# ledshield.net
KiCad netlist of a schematic drawn in EAGLE
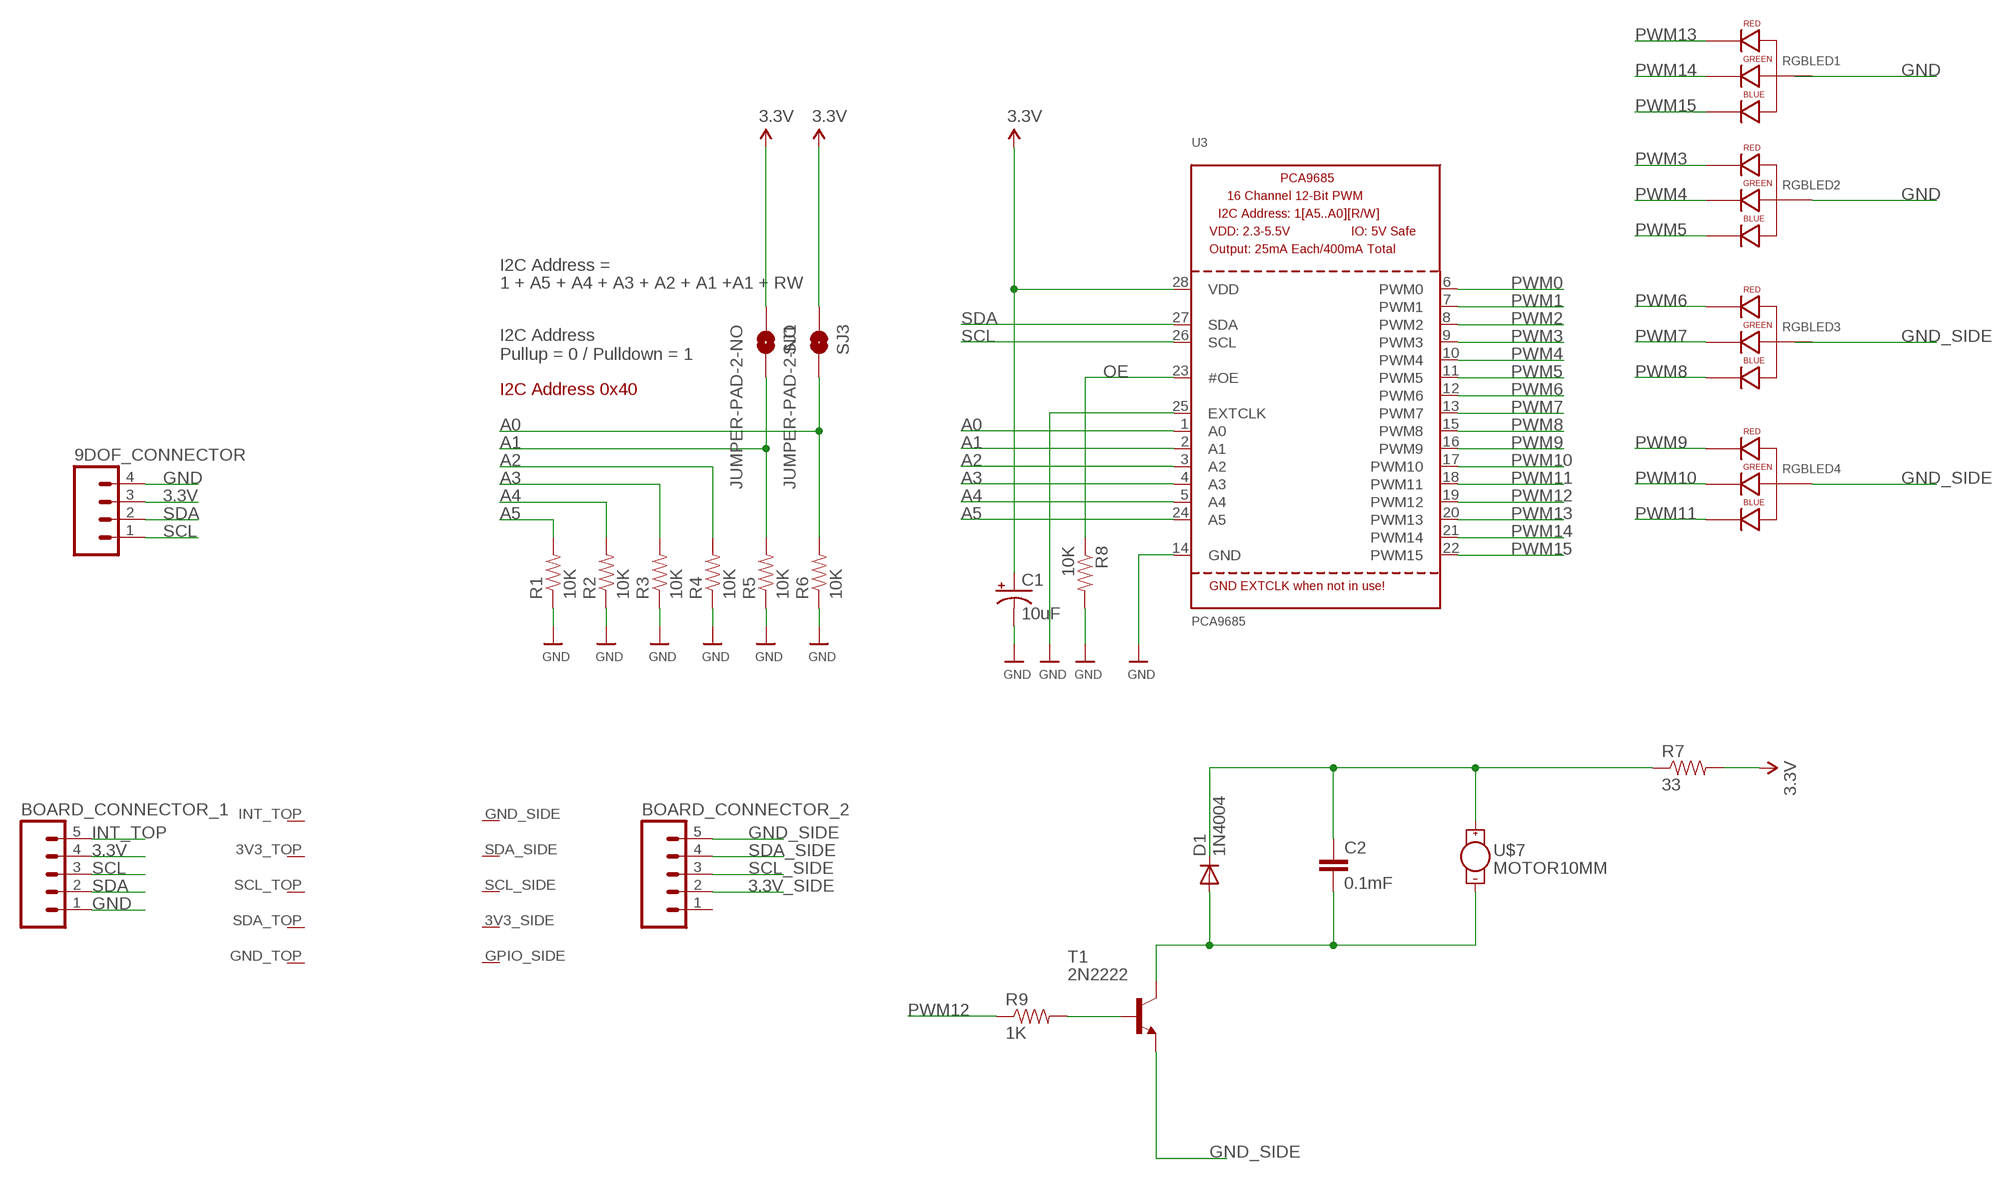
[diagram p0: schematic, sheet 1]

(export (version "E")
  (design (tool "Eeschema 10.0.6"))
  (components
    (comp (ref "9DOF_CONNECTOR")
      (value "M041.27MM")
      (footprint "eagle-import:1X04-1.27MM")
      (libsource (lib "eagle-import") (part "M041.27MM"))
    )
    (comp (ref "BOARD_CONNECTOR_1")
      (value "M051.27MM")
      (footprint "eagle-import:1X05-1.27MM")
      (libsource (lib "eagle-import") (part "M051.27MM"))
    )
    (comp (ref "BOARD_CONNECTOR_2")
      (value "M051.27MM")
      (footprint "eagle-import:1X05-1.27MM")
      (libsource (lib "eagle-import") (part "M051.27MM"))
    )
    (comp (ref "C1")
      (value "10uF")
      (footprint "eagle-import:EIA3216")
      (libsource (lib "eagle-import") (part "CAP_POL1206"))
    )
    (comp (ref "C2")
      (value "0.1mF")
      (footprint "eagle-import:1206")
      (libsource (lib "eagle-import") (part "CAP1206"))
    )
    (comp (ref "D1")
      (value "1N4004")
      (footprint "eagle-import:DO41-10")
      (libsource (lib "eagle-import") (part "1N4004"))
    )
    (comp (ref "R1")
      (value "10K")
      (footprint "eagle-import:1206")
      (libsource (lib "eagle-import") (part "RESISTOR1206"))
    )
    (comp (ref "R2")
      (value "10K")
      (footprint "eagle-import:1206")
      (libsource (lib "eagle-import") (part "RESISTOR1206"))
    )
    (comp (ref "R3")
      (value "10K")
      (footprint "eagle-import:1206")
      (libsource (lib "eagle-import") (part "RESISTOR1206"))
    )
    (comp (ref "R4")
      (value "10K")
      (footprint "eagle-import:1206")
      (libsource (lib "eagle-import") (part "RESISTOR1206"))
    )
    (comp (ref "R5")
      (value "10K")
      (footprint "eagle-import:1206")
      (libsource (lib "eagle-import") (part "RESISTOR1206"))
    )
    (comp (ref "R6")
      (value "10K")
      (footprint "eagle-import:1206")
      (libsource (lib "eagle-import") (part "RESISTOR1206"))
    )
    (comp (ref "R7")
      (value "33")
      (footprint "eagle-import:1206")
      (libsource (lib "eagle-import") (part "RESISTOR1206"))
    )
    (comp (ref "R8")
      (value "10K")
      (footprint "eagle-import:1206")
      (libsource (lib "eagle-import") (part "RESISTOR1206"))
    )
    (comp (ref "R9")
      (value "1K")
      (footprint "eagle-import:1206")
      (libsource (lib "eagle-import") (part "RESISTOR1206"))
    )
    (comp (ref "RGBLED1")
      (value "LED-RGB-CA-THRUCLEAR")
      (footprint "eagle-import:LED-RGB-THRU")
      (libsource (lib "eagle-import") (part "LED-RGB-CA-THRUCLEAR"))
    )
    (comp (ref "RGBLED2")
      (value "LED-RGB-CA-THRUCLEAR")
      (footprint "eagle-import:LED-RGB-THRU")
      (libsource (lib "eagle-import") (part "LED-RGB-CA-THRUCLEAR"))
    )
    (comp (ref "RGBLED3")
      (value "LED-RGB-CA-THRUCLEAR")
      (footprint "eagle-import:LED-RGB-THRU")
      (libsource (lib "eagle-import") (part "LED-RGB-CA-THRUCLEAR"))
    )
    (comp (ref "RGBLED4")
      (value "LED-RGB-CA-THRUCLEAR")
      (footprint "eagle-import:LED-RGB-THRU")
      (libsource (lib "eagle-import") (part "LED-RGB-CA-THRUCLEAR"))
    )
    (comp (ref "SJ1")
      (value "JUMPER-PAD-2-NO")
      (footprint "eagle-import:PAD-JUMPER-2-NO_NO_SILK")
      (libsource (lib "eagle-import") (part "JUMPER-PAD-2-NO"))
    )
    (comp (ref "SJ3")
      (value "JUMPER-PAD-2-NO")
      (footprint "eagle-import:PAD-JUMPER-2-NO_NO_SILK")
      (libsource (lib "eagle-import") (part "JUMPER-PAD-2-NO"))
    )
    (comp (ref "T1")
      (value "2N2222")
      (footprint "eagle-import:TO92-EBC-OVAL")
      (libsource (lib "eagle-import") (part "2N2222"))
    )
    (comp (ref "U$1")
      (value "IOT_MODULE_MAIN_V2_PTH")
      (footprint "eagle-import:IOT_MODULE_MAIN_V3_PTH")
      (libsource (lib "eagle-import") (part "IOT_MODULE_MAIN_V2_PTH"))
    )
    (comp (ref "U$7")
      (value "MOTOR10MM")
      (footprint "eagle-import:VIBE-MOTOR-10MM")
      (libsource (lib "eagle-import") (part "MOTOR10MM"))
    )
    (comp (ref "U3")
      (value "PCA9685")
      (footprint "eagle-import:TSSOP28")
      (libsource (lib "eagle-import") (part "PCA9685"))
    )
  )
  (nets
    (net (code "1") (name "/3.3V_SIDE") (class "Default")
      (node (ref "BOARD_CONNECTOR_2") (pin "2") (pinfunction "2_2") (pintype "passive"))
    )
    (net (code "2") (name "/A0") (class "Default")
      (node (ref "R6") (pin "2") (pinfunction "2_2") (pintype "passive"))
      (node (ref "SJ3") (pin "2") (pinfunction "2_2") (pintype "passive"))
      (node (ref "U3") (pin "1") (pinfunction "A0_1") (pintype "bidirectional"))
    )
    (net (code "3") (name "/A1") (class "Default")
      (node (ref "R5") (pin "2") (pinfunction "2_2") (pintype "passive"))
      (node (ref "SJ1") (pin "2") (pinfunction "2_2") (pintype "passive"))
      (node (ref "U3") (pin "2") (pinfunction "A1_2") (pintype "bidirectional"))
    )
    (net (code "4") (name "/A2") (class "Default")
      (node (ref "R4") (pin "2") (pinfunction "2_2") (pintype "passive"))
      (node (ref "U3") (pin "3") (pinfunction "A2_3") (pintype "bidirectional"))
    )
    (net (code "5") (name "/A3") (class "Default")
      (node (ref "R3") (pin "2") (pinfunction "2_2") (pintype "passive"))
      (node (ref "U3") (pin "4") (pinfunction "A3_4") (pintype "bidirectional"))
    )
    (net (code "6") (name "/A4") (class "Default")
      (node (ref "R2") (pin "2") (pinfunction "2_2") (pintype "passive"))
      (node (ref "U3") (pin "5") (pinfunction "A4_5") (pintype "bidirectional"))
    )
    (net (code "7") (name "/A5") (class "Default")
      (node (ref "R1") (pin "2") (pinfunction "2_2") (pintype "passive"))
      (node (ref "U3") (pin "24") (pinfunction "A5_24") (pintype "bidirectional"))
    )
    (net (code "8") (name "/GND_SIDE") (class "Default")
      (node (ref "BOARD_CONNECTOR_2") (pin "5") (pinfunction "5_5") (pintype "passive"))
      (node (ref "RGBLED4") (pin "2") (pinfunction "ANODE_2") (pintype "bidirectional"))
      (node (ref "T1") (pin "E") (pinfunction "E_E") (pintype "passive"))
    )
    (net (code "9") (name "/INT_TOP") (class "Default")
      (node (ref "BOARD_CONNECTOR_1") (pin "5") (pinfunction "5_5") (pintype "passive"))
    )
    (net (code "10") (name "/OE") (class "Default")
      (node (ref "R8") (pin "1") (pinfunction "1_1") (pintype "passive"))
      (node (ref "U3") (pin "23") (pinfunction "#OE_23") (pintype "input"))
    )
    (net (code "11") (name "/PWM0") (class "Default")
      (node (ref "U3") (pin "6") (pinfunction "PWM0_6") (pintype "output"))
    )
    (net (code "12") (name "/PWM1") (class "Default")
      (node (ref "U3") (pin "7") (pinfunction "PWM1_7") (pintype "output"))
    )
    (net (code "13") (name "/PWM2") (class "Default")
      (node (ref "U3") (pin "8") (pinfunction "PWM2_8") (pintype "output"))
    )
    (net (code "14") (name "/PWM3") (class "Default")
      (node (ref "RGBLED2") (pin "1") (pinfunction "RED_CATHODE_1") (pintype "bidirectional"))
      (node (ref "U3") (pin "9") (pinfunction "PWM3_9") (pintype "output"))
    )
    (net (code "15") (name "/PWM4") (class "Default")
      (node (ref "RGBLED2") (pin "3") (pinfunction "GREEN_CATHODE_3") (pintype "bidirectional"))
      (node (ref "U3") (pin "10") (pinfunction "PWM4_10") (pintype "output"))
    )
    (net (code "16") (name "/PWM5") (class "Default")
      (node (ref "RGBLED2") (pin "4") (pinfunction "BLUE_CATHODE_4") (pintype "bidirectional"))
      (node (ref "U3") (pin "11") (pinfunction "PWM5_11") (pintype "output"))
    )
    (net (code "17") (name "/PWM6") (class "Default")
      (node (ref "RGBLED3") (pin "1") (pinfunction "RED_CATHODE_1") (pintype "bidirectional"))
      (node (ref "U3") (pin "12") (pinfunction "PWM6_12") (pintype "output"))
    )
    (net (code "18") (name "/PWM7") (class "Default")
      (node (ref "RGBLED3") (pin "3") (pinfunction "GREEN_CATHODE_3") (pintype "bidirectional"))
      (node (ref "U3") (pin "13") (pinfunction "PWM7_13") (pintype "output"))
    )
    (net (code "19") (name "/PWM8") (class "Default")
      (node (ref "RGBLED3") (pin "4") (pinfunction "BLUE_CATHODE_4") (pintype "bidirectional"))
      (node (ref "U3") (pin "15") (pinfunction "PWM8_15") (pintype "output"))
    )
    (net (code "20") (name "/PWM9") (class "Default")
      (node (ref "RGBLED4") (pin "1") (pinfunction "RED_CATHODE_1") (pintype "bidirectional"))
      (node (ref "U3") (pin "16") (pinfunction "PWM9_16") (pintype "output"))
    )
    (net (code "21") (name "/PWM10") (class "Default")
      (node (ref "RGBLED4") (pin "3") (pinfunction "GREEN_CATHODE_3") (pintype "bidirectional"))
      (node (ref "U3") (pin "17") (pinfunction "PWM10_17") (pintype "output"))
    )
    (net (code "22") (name "/PWM11") (class "Default")
      (node (ref "RGBLED4") (pin "4") (pinfunction "BLUE_CATHODE_4") (pintype "bidirectional"))
      (node (ref "U3") (pin "18") (pinfunction "PWM11_18") (pintype "output"))
    )
    (net (code "23") (name "/PWM12") (class "Default")
      (node (ref "R9") (pin "1") (pinfunction "1_1") (pintype "passive"))
      (node (ref "U3") (pin "19") (pinfunction "PWM12_19") (pintype "output"))
    )
    (net (code "24") (name "/PWM13") (class "Default")
      (node (ref "RGBLED1") (pin "1") (pinfunction "RED_CATHODE_1") (pintype "bidirectional"))
      (node (ref "U3") (pin "20") (pinfunction "PWM13_20") (pintype "output"))
    )
    (net (code "25") (name "/PWM14") (class "Default")
      (node (ref "RGBLED1") (pin "3") (pinfunction "GREEN_CATHODE_3") (pintype "bidirectional"))
      (node (ref "U3") (pin "21") (pinfunction "PWM14_21") (pintype "output"))
    )
    (net (code "26") (name "/PWM15") (class "Default")
      (node (ref "RGBLED1") (pin "4") (pinfunction "BLUE_CATHODE_4") (pintype "bidirectional"))
      (node (ref "U3") (pin "22") (pinfunction "PWM15_22") (pintype "output"))
    )
    (net (code "27") (name "/SCL") (class "Default")
      (node (ref "9DOF_CONNECTOR") (pin "1") (pinfunction "1_1") (pintype "passive"))
      (node (ref "BOARD_CONNECTOR_1") (pin "3") (pinfunction "3_3") (pintype "passive"))
      (node (ref "U3") (pin "26") (pinfunction "SCL_26") (pintype "bidirectional"))
    )
    (net (code "28") (name "/SCL_SIDE") (class "Default")
      (node (ref "BOARD_CONNECTOR_2") (pin "3") (pinfunction "3_3") (pintype "passive"))
    )
    (net (code "29") (name "/SDA") (class "Default")
      (node (ref "9DOF_CONNECTOR") (pin "2") (pinfunction "2_2") (pintype "passive"))
      (node (ref "BOARD_CONNECTOR_1") (pin "2") (pinfunction "2_2") (pintype "passive"))
      (node (ref "U3") (pin "27") (pinfunction "SDA_27") (pintype "bidirectional"))
    )
    (net (code "30") (name "/SDA_SIDE") (class "Default")
      (node (ref "BOARD_CONNECTOR_2") (pin "4") (pinfunction "4_4") (pintype "passive"))
    )
    (net (code "31") (name "3.3V") (class "Default")
      (node (ref "9DOF_CONNECTOR") (pin "3") (pinfunction "3_3") (pintype "passive"))
      (node (ref "BOARD_CONNECTOR_1") (pin "4") (pinfunction "4_4") (pintype "passive"))
      (node (ref "C1") (pin "A") (pinfunction "+_A") (pintype "passive"))
      (node (ref "R7") (pin "2") (pinfunction "2_2") (pintype "passive"))
      (node (ref "SJ1") (pin "1") (pinfunction "1_1") (pintype "passive"))
      (node (ref "SJ3") (pin "1") (pinfunction "1_1") (pintype "passive"))
      (node (ref "U3") (pin "28") (pinfunction "VDD_28") (pintype "power_in"))
    )
    (net (code "32") (name "GND") (class "Default")
      (node (ref "9DOF_CONNECTOR") (pin "4") (pinfunction "4_4") (pintype "passive"))
      (node (ref "BOARD_CONNECTOR_1") (pin "1") (pinfunction "1_1") (pintype "passive"))
      (node (ref "C1") (pin "C") (pinfunction "-_C") (pintype "passive"))
      (node (ref "R1") (pin "1") (pinfunction "1_1") (pintype "passive"))
      (node (ref "R2") (pin "1") (pinfunction "1_1") (pintype "passive"))
      (node (ref "R3") (pin "1") (pinfunction "1_1") (pintype "passive"))
      (node (ref "R4") (pin "1") (pinfunction "1_1") (pintype "passive"))
      (node (ref "R5") (pin "1") (pinfunction "1_1") (pintype "passive"))
      (node (ref "R6") (pin "1") (pinfunction "1_1") (pintype "passive"))
      (node (ref "R8") (pin "2") (pinfunction "2_2") (pintype "passive"))
      (node (ref "RGBLED2") (pin "2") (pinfunction "ANODE_2") (pintype "bidirectional"))
      (node (ref "U3") (pin "14") (pinfunction "GND_14") (pintype "power_in"))
      (node (ref "U3") (pin "25") (pinfunction "EXTCLK_25") (pintype "input"))
    )
    (net (code "33") (name "Net-(C2-Pad1)") (class "Default")
      (node (ref "C2") (pin "1") (pinfunction "1_1") (pintype "passive"))
      (node (ref "D1") (pin "C") (pinfunction "C_C") (pintype "passive"))
      (node (ref "R7") (pin "1") (pinfunction "1_1") (pintype "passive"))
      (node (ref "U$7") (pin "+") (pinfunction "+_+") (pintype "bidirectional"))
    )
    (net (code "34") (name "Net-(C2-Pad2)") (class "Default")
      (node (ref "C2") (pin "2") (pinfunction "2_2") (pintype "passive"))
      (node (ref "D1") (pin "A") (pinfunction "A_A") (pintype "passive"))
      (node (ref "T1") (pin "C") (pinfunction "C_C") (pintype "passive"))
      (node (ref "U$7") (pin "-") (pinfunction "-_-") (pintype "bidirectional"))
    )
    (net (code "35") (name "Net-(R9-Pad2)") (class "Default")
      (node (ref "R9") (pin "2") (pinfunction "2_2") (pintype "passive"))
      (node (ref "T1") (pin "B") (pinfunction "B_B") (pintype "passive"))
    )
    (net (code "36") (name "unconnected-(BOARD_CONNECTOR_2-Pad1)") (class "Default")
      (node (ref "BOARD_CONNECTOR_2") (pin "1") (pinfunction "1_1") (pintype "passive"))
    )
    (net (code "37") (name "unconnected-(RGBLED1-ANODE-Pad2)") (class "Default")
      (node (ref "RGBLED1") (pin "2") (pinfunction "ANODE_2") (pintype "bidirectional"))
    )
    (net (code "38") (name "unconnected-(RGBLED3-ANODE-Pad2)") (class "Default")
      (node (ref "RGBLED3") (pin "2") (pinfunction "ANODE_2") (pintype "bidirectional"))
    )
    (net (code "39") (name "unconnected-(U$1-Pad3V3_SIDE)") (class "Default")
      (node (ref "U$1") (pin "3V3_SIDE") (pinfunction "3V3_SIDE_3V3_SIDE") (pintype "bidirectional"))
    )
    (net (code "40") (name "unconnected-(U$1-Pad3V3_TOP)") (class "Default")
      (node (ref "U$1") (pin "3V3_TOP") (pinfunction "3V3_TOP_3V3_TOP") (pintype "bidirectional"))
    )
    (net (code "41") (name "unconnected-(U$1-PadGND_SIDE)") (class "Default")
      (node (ref "U$1") (pin "GND_SIDE") (pinfunction "GND_SIDE_GND_SIDE") (pintype "bidirectional"))
    )
    (net (code "42") (name "unconnected-(U$1-PadGND_TOP)") (class "Default")
      (node (ref "U$1") (pin "GND_TOP") (pinfunction "GND_TOP_GND_TOP") (pintype "bidirectional"))
    )
    (net (code "43") (name "unconnected-(U$1-PadGPIO_SIDE)") (class "Default")
      (node (ref "U$1") (pin "GPIO_SIDE") (pinfunction "GPIO_SIDE_GPIO_SIDE") (pintype "bidirectional"))
    )
    (net (code "44") (name "unconnected-(U$1-PadINT_TOP)") (class "Default")
      (node (ref "U$1") (pin "INT_TOP") (pinfunction "INT_TOP_INT_TOP") (pintype "bidirectional"))
    )
    (net (code "45") (name "unconnected-(U$1-PadSCL_SIDE)") (class "Default")
      (node (ref "U$1") (pin "SCL_SIDE") (pinfunction "SCL_SIDE_SCL_SIDE") (pintype "bidirectional"))
    )
    (net (code "46") (name "unconnected-(U$1-PadSCL_TOP)") (class "Default")
      (node (ref "U$1") (pin "SCL_TOP") (pinfunction "SCL_TOP_SCL_TOP") (pintype "bidirectional"))
    )
    (net (code "47") (name "unconnected-(U$1-PadSDA_SIDE)") (class "Default")
      (node (ref "U$1") (pin "SDA_SIDE") (pinfunction "SDA_SIDE_SDA_SIDE") (pintype "bidirectional"))
    )
    (net (code "48") (name "unconnected-(U$1-PadSDA_TOP)") (class "Default")
      (node (ref "U$1") (pin "SDA_TOP") (pinfunction "SDA_TOP_SDA_TOP") (pintype "bidirectional"))
    )
  )
)
